# SchematicDrone.net
KiCad netlist of a schematic drawn in EAGLE
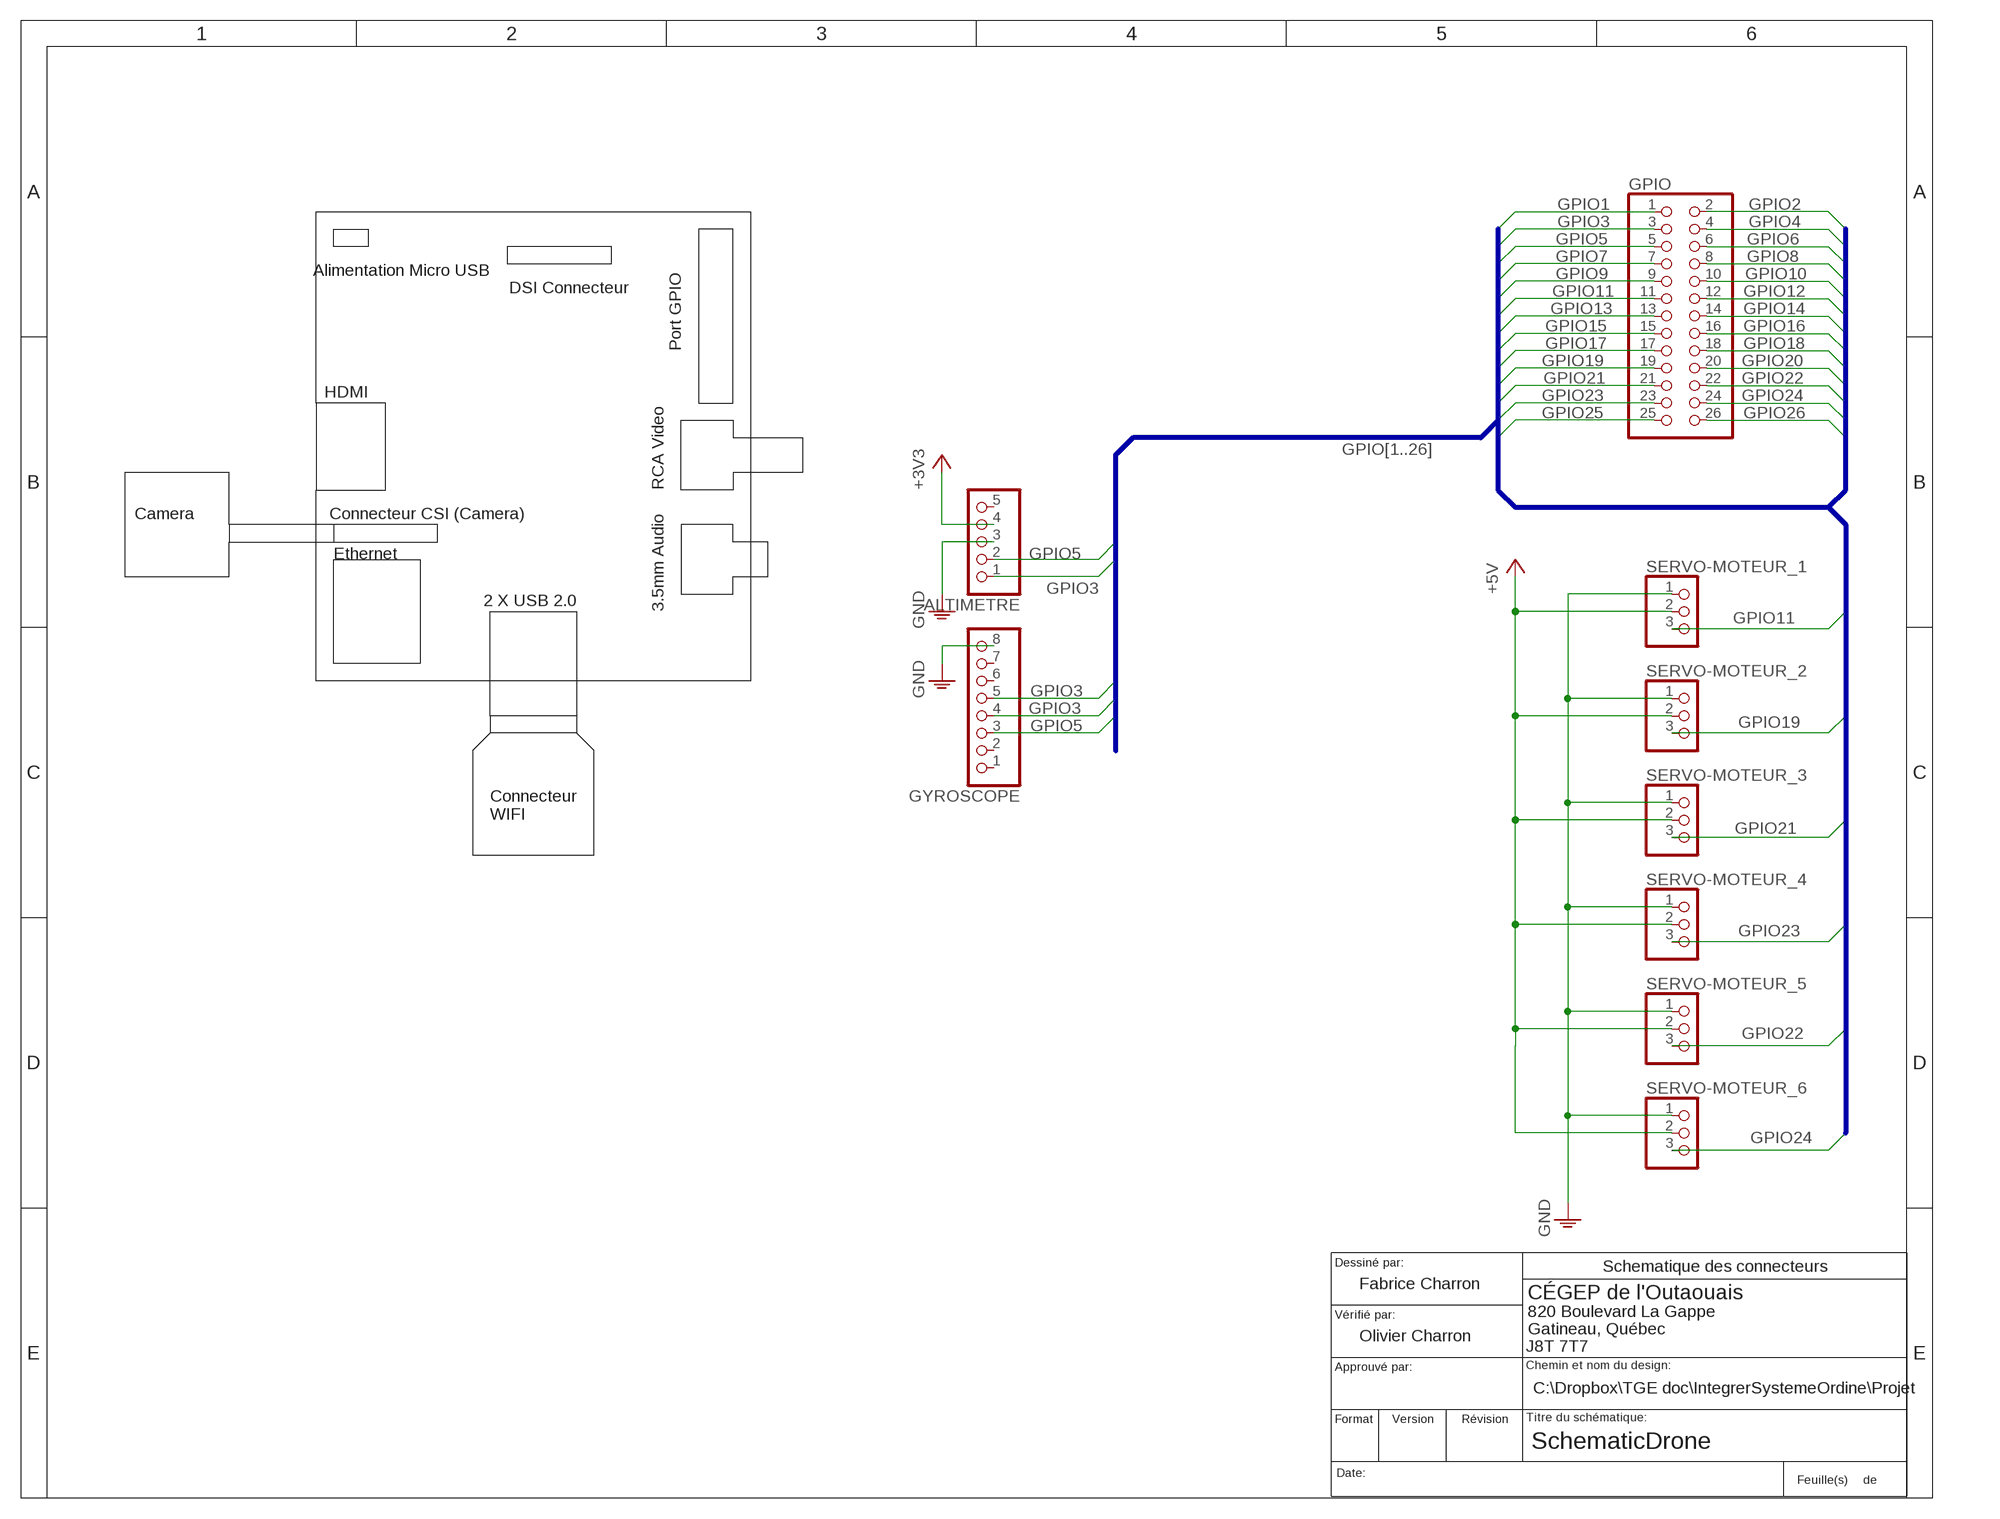
[diagram p0: schematic, sheet 1]

(export (version "E")
  (design (tool "Eeschema 10.0.6"))
  (components
    (comp (ref "ALTIMETRE")
      (value "PINHD-1X5")
      (footprint "eagle-import:1X05")
      (libsource (lib "eagle-import") (part "PINHD-1X5"))
    )
    (comp (ref "GPIO")
      (value "PINHD-2X13/90")
      (footprint "eagle-import:2X13_90")
      (libsource (lib "eagle-import") (part "PINHD-2X13/90"))
    )
    (comp (ref "GYROSCOPE")
      (value "PINHD-1X8")
      (footprint "eagle-import:1X08")
      (libsource (lib "eagle-import") (part "PINHD-1X8"))
    )
    (comp (ref "SERVO-MOTEUR_1")
      (value "PINHD-1X3/90")
      (footprint "eagle-import:1X03_90")
      (libsource (lib "eagle-import") (part "PINHD-1X3/90"))
    )
    (comp (ref "SERVO-MOTEUR_2")
      (value "PINHD-1X3/90")
      (footprint "eagle-import:1X03_90")
      (libsource (lib "eagle-import") (part "PINHD-1X3/90"))
    )
    (comp (ref "SERVO-MOTEUR_3")
      (value "PINHD-1X3/90")
      (footprint "eagle-import:1X03_90")
      (libsource (lib "eagle-import") (part "PINHD-1X3/90"))
    )
    (comp (ref "SERVO-MOTEUR_4")
      (value "PINHD-1X3/90")
      (footprint "eagle-import:1X03_90")
      (libsource (lib "eagle-import") (part "PINHD-1X3/90"))
    )
    (comp (ref "SERVO-MOTEUR_5")
      (value "PINHD-1X3/90")
      (footprint "eagle-import:1X03_90")
      (libsource (lib "eagle-import") (part "PINHD-1X3/90"))
    )
    (comp (ref "SERVO-MOTEUR_6")
      (value "PINHD-1X3/90")
      (footprint "eagle-import:1X03_90")
      (libsource (lib "eagle-import") (part "PINHD-1X3/90"))
    )
  )
  (nets
    (net (code "1") (name "+3V3") (class "Default")
      (node (ref "ALTIMETRE") (pin "4") (pinfunction "4_4") (pintype "passive"))
    )
    (net (code "2") (name "+5V") (class "Default")
      (node (ref "SERVO-MOTEUR_1") (pin "2") (pinfunction "2_2") (pintype "passive"))
      (node (ref "SERVO-MOTEUR_2") (pin "2") (pinfunction "2_2") (pintype "passive"))
      (node (ref "SERVO-MOTEUR_3") (pin "2") (pinfunction "2_2") (pintype "passive"))
      (node (ref "SERVO-MOTEUR_4") (pin "2") (pinfunction "2_2") (pintype "passive"))
      (node (ref "SERVO-MOTEUR_5") (pin "2") (pinfunction "2_2") (pintype "passive"))
      (node (ref "SERVO-MOTEUR_6") (pin "2") (pinfunction "2_2") (pintype "passive"))
    )
    (net (code "3") (name "/GPIO1") (class "Default")
      (node (ref "GPIO") (pin "1") (pinfunction "1_1") (pintype "passive"))
    )
    (net (code "4") (name "/GPIO2") (class "Default")
      (node (ref "GPIO") (pin "2") (pinfunction "2_2") (pintype "passive"))
    )
    (net (code "5") (name "/GPIO3") (class "Default")
      (node (ref "ALTIMETRE") (pin "1") (pinfunction "1_1") (pintype "passive"))
      (node (ref "GPIO") (pin "3") (pinfunction "3_3") (pintype "passive"))
      (node (ref "GYROSCOPE") (pin "4") (pinfunction "4_4") (pintype "passive"))
      (node (ref "GYROSCOPE") (pin "5") (pinfunction "5_5") (pintype "passive"))
    )
    (net (code "6") (name "/GPIO4") (class "Default")
      (node (ref "GPIO") (pin "4") (pinfunction "4_4") (pintype "passive"))
    )
    (net (code "7") (name "/GPIO5") (class "Default")
      (node (ref "ALTIMETRE") (pin "2") (pinfunction "2_2") (pintype "passive"))
      (node (ref "GPIO") (pin "5") (pinfunction "5_5") (pintype "passive"))
      (node (ref "GYROSCOPE") (pin "3") (pinfunction "3_3") (pintype "passive"))
    )
    (net (code "8") (name "/GPIO6") (class "Default")
      (node (ref "GPIO") (pin "6") (pinfunction "6_6") (pintype "passive"))
    )
    (net (code "9") (name "/GPIO7") (class "Default")
      (node (ref "GPIO") (pin "7") (pinfunction "7_7") (pintype "passive"))
    )
    (net (code "10") (name "/GPIO8") (class "Default")
      (node (ref "GPIO") (pin "8") (pinfunction "8_8") (pintype "passive"))
    )
    (net (code "11") (name "/GPIO9") (class "Default")
      (node (ref "GPIO") (pin "9") (pinfunction "9_9") (pintype "passive"))
    )
    (net (code "12") (name "/GPIO10") (class "Default")
      (node (ref "GPIO") (pin "10") (pinfunction "10_10") (pintype "passive"))
    )
    (net (code "13") (name "/GPIO11") (class "Default")
      (node (ref "GPIO") (pin "11") (pinfunction "11_11") (pintype "passive"))
      (node (ref "SERVO-MOTEUR_1") (pin "3") (pinfunction "3_3") (pintype "passive"))
    )
    (net (code "14") (name "/GPIO12") (class "Default")
      (node (ref "GPIO") (pin "12") (pinfunction "12_12") (pintype "passive"))
    )
    (net (code "15") (name "/GPIO13") (class "Default")
      (node (ref "GPIO") (pin "13") (pinfunction "13_13") (pintype "passive"))
    )
    (net (code "16") (name "/GPIO14") (class "Default")
      (node (ref "GPIO") (pin "14") (pinfunction "14_14") (pintype "passive"))
    )
    (net (code "17") (name "/GPIO15") (class "Default")
      (node (ref "GPIO") (pin "15") (pinfunction "15_15") (pintype "passive"))
    )
    (net (code "18") (name "/GPIO16") (class "Default")
      (node (ref "GPIO") (pin "16") (pinfunction "16_16") (pintype "passive"))
    )
    (net (code "19") (name "/GPIO17") (class "Default")
      (node (ref "GPIO") (pin "17") (pinfunction "17_17") (pintype "passive"))
    )
    (net (code "20") (name "/GPIO18") (class "Default")
      (node (ref "GPIO") (pin "18") (pinfunction "18_18") (pintype "passive"))
    )
    (net (code "21") (name "/GPIO19") (class "Default")
      (node (ref "GPIO") (pin "19") (pinfunction "19_19") (pintype "passive"))
      (node (ref "SERVO-MOTEUR_2") (pin "3") (pinfunction "3_3") (pintype "passive"))
    )
    (net (code "22") (name "/GPIO20") (class "Default")
      (node (ref "GPIO") (pin "20") (pinfunction "20_20") (pintype "passive"))
    )
    (net (code "23") (name "/GPIO21") (class "Default")
      (node (ref "GPIO") (pin "21") (pinfunction "21_21") (pintype "passive"))
      (node (ref "SERVO-MOTEUR_3") (pin "3") (pinfunction "3_3") (pintype "passive"))
    )
    (net (code "24") (name "/GPIO22") (class "Default")
      (node (ref "GPIO") (pin "22") (pinfunction "22_22") (pintype "passive"))
      (node (ref "SERVO-MOTEUR_5") (pin "3") (pinfunction "3_3") (pintype "passive"))
    )
    (net (code "25") (name "/GPIO23") (class "Default")
      (node (ref "GPIO") (pin "23") (pinfunction "23_23") (pintype "passive"))
      (node (ref "SERVO-MOTEUR_4") (pin "3") (pinfunction "3_3") (pintype "passive"))
    )
    (net (code "26") (name "/GPIO24") (class "Default")
      (node (ref "GPIO") (pin "24") (pinfunction "24_24") (pintype "passive"))
      (node (ref "SERVO-MOTEUR_6") (pin "3") (pinfunction "3_3") (pintype "passive"))
    )
    (net (code "27") (name "/GPIO25") (class "Default")
      (node (ref "GPIO") (pin "25") (pinfunction "25_25") (pintype "passive"))
    )
    (net (code "28") (name "/GPIO26") (class "Default")
      (node (ref "GPIO") (pin "26") (pinfunction "26_26") (pintype "passive"))
    )
    (net (code "30") (name "GND") (class "Default")
      (node (ref "ALTIMETRE") (pin "3") (pinfunction "3_3") (pintype "passive"))
      (node (ref "GYROSCOPE") (pin "8") (pinfunction "8_8") (pintype "passive"))
      (node (ref "SERVO-MOTEUR_1") (pin "1") (pinfunction "1_1") (pintype "passive"))
      (node (ref "SERVO-MOTEUR_2") (pin "1") (pinfunction "1_1") (pintype "passive"))
      (node (ref "SERVO-MOTEUR_3") (pin "1") (pinfunction "1_1") (pintype "passive"))
      (node (ref "SERVO-MOTEUR_4") (pin "1") (pinfunction "1_1") (pintype "passive"))
      (node (ref "SERVO-MOTEUR_5") (pin "1") (pinfunction "1_1") (pintype "passive"))
      (node (ref "SERVO-MOTEUR_6") (pin "1") (pinfunction "1_1") (pintype "passive"))
    )
    (net (code "31") (name "unconnected-(ALTIMETRE-Pad5)") (class "Default")
      (node (ref "ALTIMETRE") (pin "5") (pinfunction "5_5") (pintype "passive"))
    )
    (net (code "32") (name "unconnected-(GYROSCOPE-Pad1)") (class "Default")
      (node (ref "GYROSCOPE") (pin "1") (pinfunction "1_1") (pintype "passive"))
    )
    (net (code "33") (name "unconnected-(GYROSCOPE-Pad2)") (class "Default")
      (node (ref "GYROSCOPE") (pin "2") (pinfunction "2_2") (pintype "passive"))
    )
    (net (code "34") (name "unconnected-(GYROSCOPE-Pad6)") (class "Default")
      (node (ref "GYROSCOPE") (pin "6") (pinfunction "6_6") (pintype "passive"))
    )
    (net (code "35") (name "unconnected-(GYROSCOPE-Pad7)") (class "Default")
      (node (ref "GYROSCOPE") (pin "7") (pinfunction "7_7") (pintype "passive"))
    )
  )
)
